# LED.net
KiCad netlist of a schematic drawn in Altium Designer
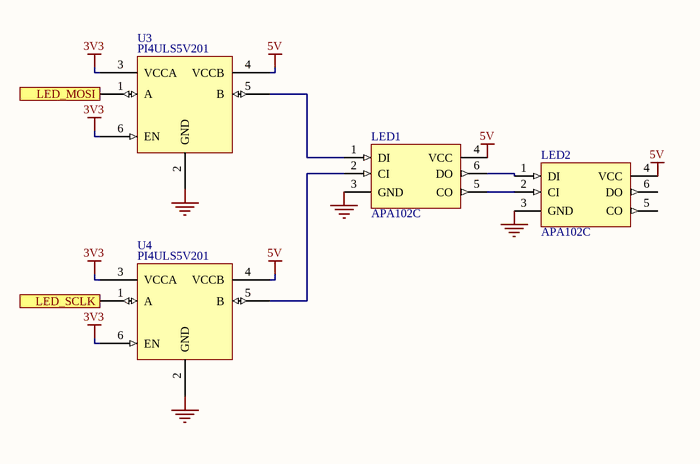
[diagram p0: LED.SchDoc]

(export (version "E")
  (design (tool "Eeschema 10.0.6"))
  (components
    (comp (ref "LED1") (value "APA102C") (footprint "5x5_WS2812") (libsource (lib "Parts") (part "APA102C")))
    (comp (ref "LED2") (value "APA102C") (footprint "5x5_WS2812") (libsource (lib "Parts") (part "APA102C")))
    (comp (ref "U3")
      (value "PI4ULS5V201")
      (footprint "SOT23-PI4ULS5V201")
      (description "Level Translator")
      (libsource (lib "Parts") (part "PI4ULS5V201"))
    )
    (comp (ref "U4")
      (value "PI4ULS5V201")
      (footprint "SOT23-PI4ULS5V201")
      (description "Level Translator")
      (libsource (lib "Parts") (part "PI4ULS5V201"))
    )
  )
  (nets
    (net (code "1") (name "/LED_MOSI") (class "Default")
      (node (ref "U3") (pin "1") (pinfunction "A_1") (pintype "bidirectional"))
    )
    (net (code "2") (name "/LED_SCLK") (class "Default")
      (node (ref "U4") (pin "1") (pinfunction "A_1") (pintype "bidirectional"))
    )
    (net (code "3") (name "3V3") (class "Default")
      (node (ref "U3") (pin "3") (pinfunction "VCCA_3") (pintype "power_in"))
      (node (ref "U3") (pin "6") (pinfunction "EN_6") (pintype "input"))
      (node (ref "U4") (pin "3") (pinfunction "VCCA_3") (pintype "power_in"))
      (node (ref "U4") (pin "6") (pinfunction "EN_6") (pintype "input"))
    )
    (net (code "4") (name "5V") (class "Default")
      (node (ref "LED1") (pin "4") (pinfunction "VCC_4") (pintype "power_in"))
      (node (ref "LED2") (pin "4") (pinfunction "VCC_4") (pintype "power_in"))
      (node (ref "U3") (pin "4") (pinfunction "VCCB_4") (pintype "power_in"))
      (node (ref "U4") (pin "4") (pinfunction "VCCB_4") (pintype "power_in"))
    )
    (net (code "5") (name "GND") (class "Default")
      (node (ref "LED1") (pin "3") (pinfunction "GND_3") (pintype "power_in"))
      (node (ref "LED2") (pin "3") (pinfunction "GND_3") (pintype "power_in"))
      (node (ref "U3") (pin "2") (pinfunction "GND_2") (pintype "power_in"))
      (node (ref "U4") (pin "2") (pinfunction "GND_2") (pintype "power_in"))
    )
    (net (code "6") (name "Net-(LED1-CI)") (class "Default")
      (node (ref "LED1") (pin "2") (pinfunction "CI_2") (pintype "input"))
      (node (ref "U4") (pin "5") (pinfunction "B_5") (pintype "bidirectional"))
    )
    (net (code "7") (name "Net-(LED1-CO)") (class "Default")
      (node (ref "LED1") (pin "5") (pinfunction "CO_5") (pintype "output"))
      (node (ref "LED2") (pin "2") (pinfunction "CI_2") (pintype "input"))
    )
    (net (code "8") (name "Net-(LED1-DI)") (class "Default")
      (node (ref "LED1") (pin "1") (pinfunction "DI_1") (pintype "input"))
      (node (ref "U3") (pin "5") (pinfunction "B_5") (pintype "bidirectional"))
    )
    (net (code "9") (name "Net-(LED1-DO)") (class "Default")
      (node (ref "LED1") (pin "6") (pinfunction "DO_6") (pintype "output"))
      (node (ref "LED2") (pin "1") (pinfunction "DI_1") (pintype "input"))
    )
    (net (code "10") (name "unconnected-(LED2-CO-Pad5)") (class "Default")
      (node (ref "LED2") (pin "5") (pinfunction "CO_5") (pintype "output"))
    )
    (net (code "11") (name "unconnected-(LED2-DO-Pad6)") (class "Default")
      (node (ref "LED2") (pin "6") (pinfunction "DO_6") (pintype "output"))
    )
  )
)
